# Sandshark_3D_-_MCU_-_ATSAM3X8C.net
KiCad netlist of a schematic drawn in Altium Designer
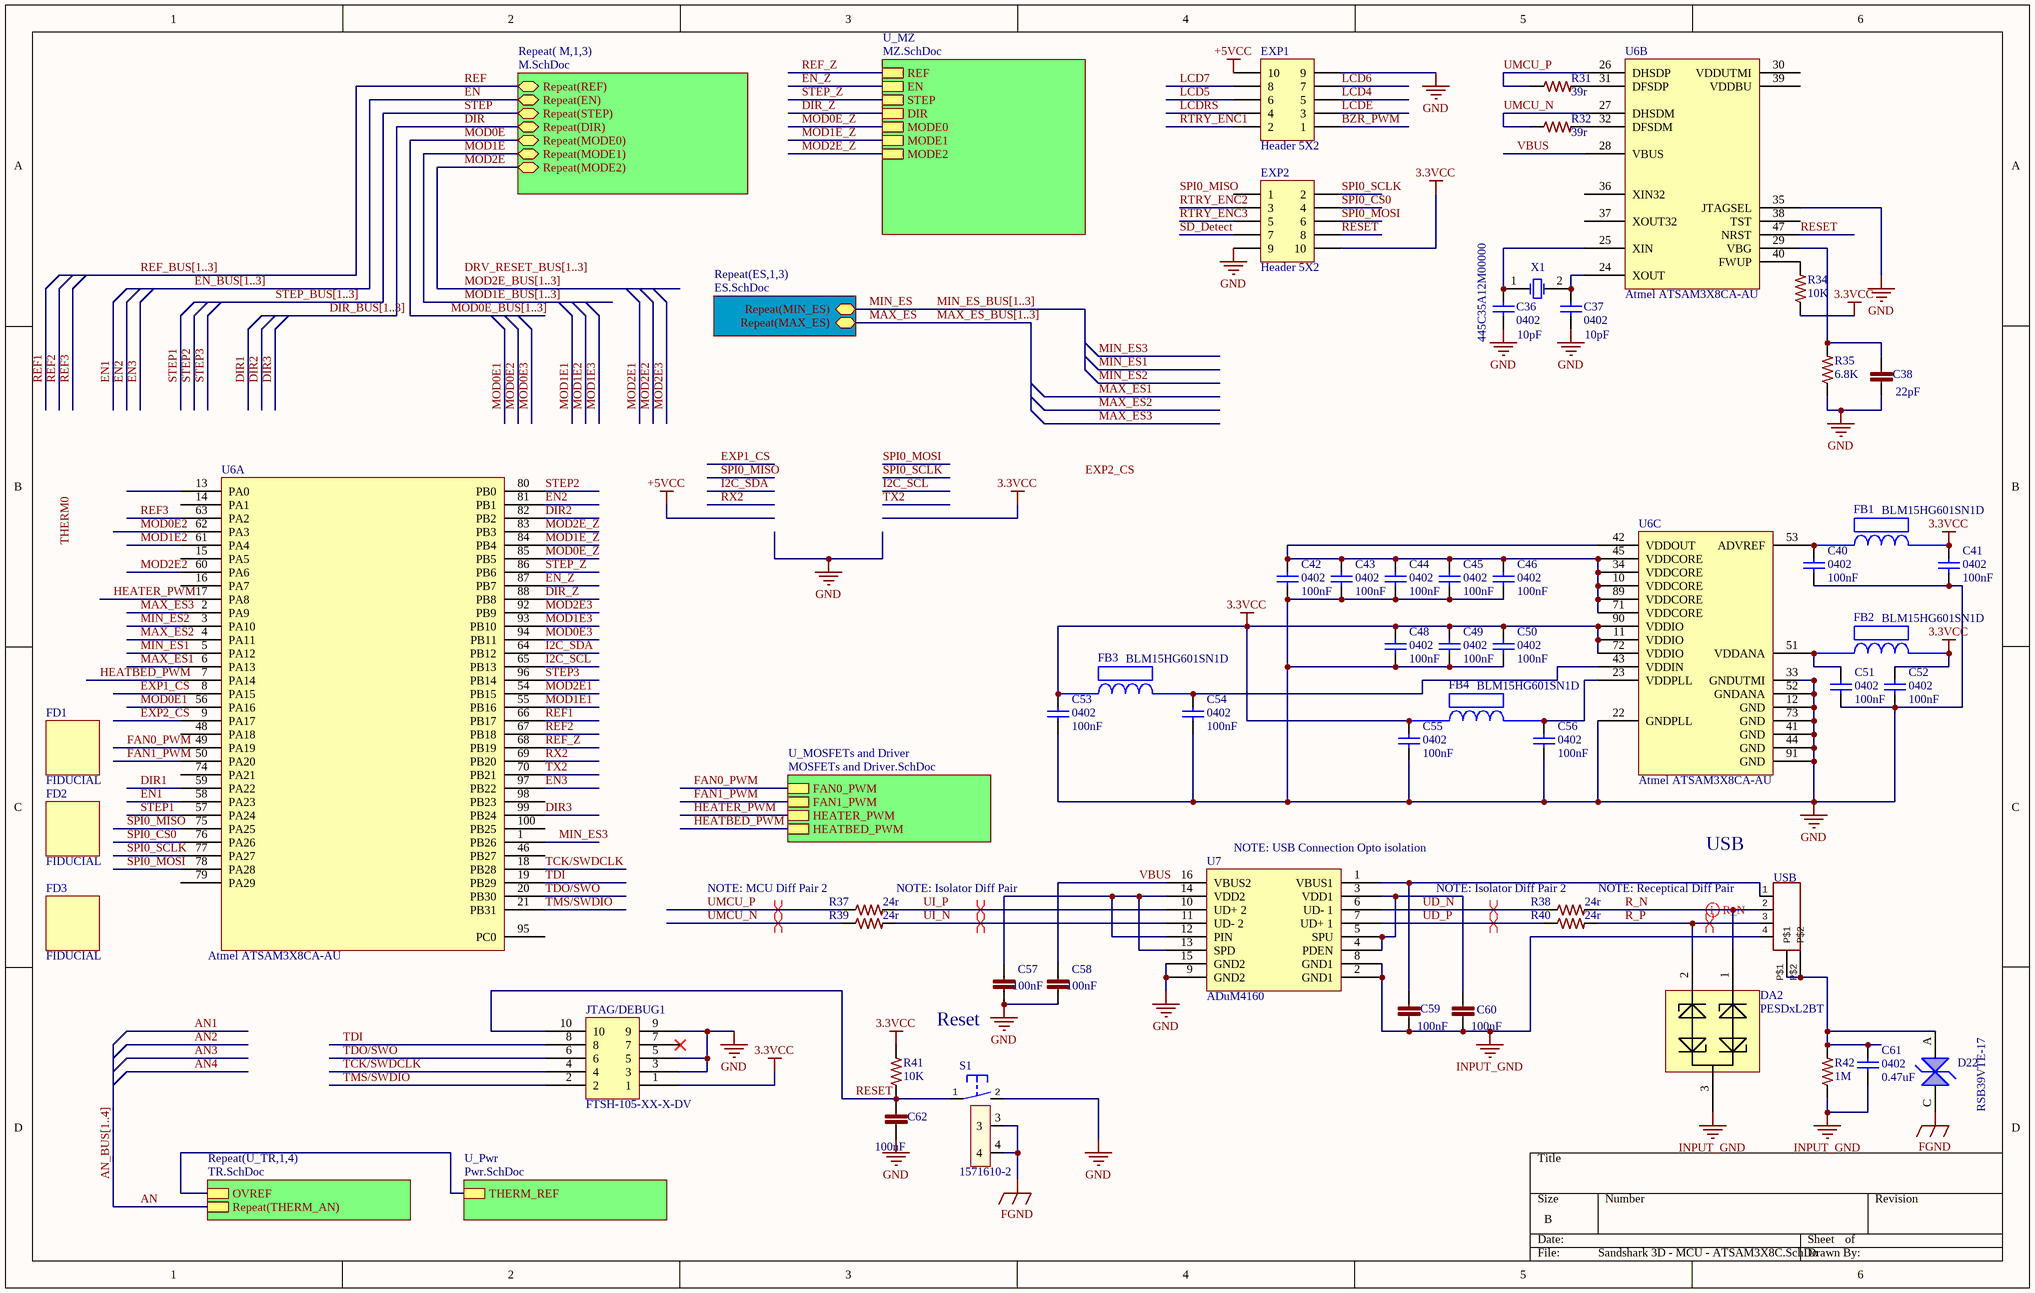
[diagram p0: Sandshark 3D - MCU - ATSAM3X8C.SchDoc]

(export (version "E")
  (design (tool "Eeschema 10.0.6"))
  (components
    (comp (ref "C36")
      (value "0402")
      (footprint "C0402")
      (description "CAP CER 10PF 50V 5% NP0 0402")
      (fields
        (field (name "MFR PART #") "CL05C100JB5NNNC")
        (field (name "MFR") "Samsung")
        (field (name "ALTIUM_VALUE") "10pF")
        (field (name "PUBLISHER") "Ultimachine")
      )
      (libsource (lib "Tigershark3D") (part "CL05C100JB5NNNC"))
    )
    (comp (ref "C37")
      (value "0402")
      (footprint "C0402")
      (description "CAP CER 10PF 50V 5% NP0 0402")
      (fields
        (field (name "MFR PART #") "CL05C100JB5NNNC")
        (field (name "MFR") "Samsung")
        (field (name "ALTIUM_VALUE") "10pF")
        (field (name "PUBLISHER") "Ultimachine")
      )
      (libsource (lib "Tigershark3D") (part "CL05C100JB5NNNC"))
    )
    (comp (ref "C38")
      (value "22pF")
      (footprint "C0402")
      (description "CAP CER 0402 22pF 50V 5% C0G")
      (fields
        (field (name "MANUFACTURERPARTNUMBER") "04025A220JAT2A")
        (field (name "PUBLISHER") "UltiMachine")
      )
      (libsource (lib "3Delight") (part "04025A220JAT2A"))
    )
    (comp (ref "C40")
      (value "100nF")
      (footprint "C0402")
      (description "CAP CER 0.1UF (100nF) 16V 10% X7R 0402")
      (fields
        (field (name "MFR PART #") "GRM155R71C104KA88D")
        (field (name "MFR") "Murata")
        (field (name "PACKAGEREFERENCE") "0402")
        (field (name "PUBLISHER") "Ultimachine")
      )
      (libsource (lib "Tigershark3D") (part "GRM155R71C104KA88D"))
    )
    (comp (ref "C41")
      (value "100nF")
      (footprint "C0402")
      (description "CAP CER 0.1UF (100nF) 16V 10% X7R 0402")
      (fields
        (field (name "MFR PART #") "GRM155R71C104KA88D")
        (field (name "MFR") "Murata")
        (field (name "PACKAGEREFERENCE") "0402")
        (field (name "PUBLISHER") "Ultimachine")
      )
      (libsource (lib "Tigershark3D") (part "GRM155R71C104KA88D"))
    )
    (comp (ref "C42")
      (value "100nF")
      (footprint "C0402")
      (description "CAP CER 0.1UF (100nF) 16V 10% X7R 0402")
      (fields
        (field (name "MFR PART #") "GRM155R71C104KA88D")
        (field (name "MFR") "Murata")
        (field (name "PACKAGEREFERENCE") "0402")
        (field (name "PUBLISHER") "Ultimachine")
      )
      (libsource (lib "Tigershark3D") (part "GRM155R71C104KA88D"))
    )
    (comp (ref "C43")
      (value "100nF")
      (footprint "C0402")
      (description "CAP CER 0.1UF (100nF) 16V 10% X7R 0402")
      (fields
        (field (name "MFR PART #") "GRM155R71C104KA88D")
        (field (name "MFR") "Murata")
        (field (name "PACKAGEREFERENCE") "0402")
        (field (name "PUBLISHER") "Ultimachine")
      )
      (libsource (lib "Tigershark3D") (part "GRM155R71C104KA88D"))
    )
    (comp (ref "C44")
      (value "100nF")
      (footprint "C0402")
      (description "CAP CER 0.1UF (100nF) 16V 10% X7R 0402")
      (fields
        (field (name "MFR PART #") "GRM155R71C104KA88D")
        (field (name "MFR") "Murata")
        (field (name "PACKAGEREFERENCE") "0402")
        (field (name "PUBLISHER") "Ultimachine")
      )
      (libsource (lib "Tigershark3D") (part "GRM155R71C104KA88D"))
    )
    (comp (ref "C45")
      (value "100nF")
      (footprint "C0402")
      (description "CAP CER 0.1UF (100nF) 16V 10% X7R 0402")
      (fields
        (field (name "MFR PART #") "GRM155R71C104KA88D")
        (field (name "MFR") "Murata")
        (field (name "PACKAGEREFERENCE") "0402")
        (field (name "PUBLISHER") "Ultimachine")
      )
      (libsource (lib "Tigershark3D") (part "GRM155R71C104KA88D"))
    )
    (comp (ref "C46")
      (value "100nF")
      (footprint "C0402")
      (description "CAP CER 0.1UF (100nF) 16V 10% X7R 0402")
      (fields
        (field (name "MFR PART #") "GRM155R71C104KA88D")
        (field (name "MFR") "Murata")
        (field (name "PACKAGEREFERENCE") "0402")
        (field (name "PUBLISHER") "Ultimachine")
      )
      (libsource (lib "Tigershark3D") (part "GRM155R71C104KA88D"))
    )
    (comp (ref "C48")
      (value "100nF")
      (footprint "C0402")
      (description "CAP CER 0.1UF (100nF) 16V 10% X7R 0402")
      (fields
        (field (name "MFR PART #") "GRM155R71C104KA88D")
        (field (name "MFR") "Murata")
        (field (name "PACKAGEREFERENCE") "0402")
        (field (name "PUBLISHER") "Ultimachine")
      )
      (libsource (lib "Tigershark3D") (part "GRM155R71C104KA88D"))
    )
    (comp (ref "C49")
      (value "100nF")
      (footprint "C0402")
      (description "CAP CER 0.1UF (100nF) 16V 10% X7R 0402")
      (fields
        (field (name "MFR PART #") "GRM155R71C104KA88D")
        (field (name "MFR") "Murata")
        (field (name "PACKAGEREFERENCE") "0402")
        (field (name "PUBLISHER") "Ultimachine")
      )
      (libsource (lib "Tigershark3D") (part "GRM155R71C104KA88D"))
    )
    (comp (ref "C50")
      (value "100nF")
      (footprint "C0402")
      (description "CAP CER 0.1UF (100nF) 16V 10% X7R 0402")
      (fields
        (field (name "MFR PART #") "GRM155R71C104KA88D")
        (field (name "MFR") "Murata")
        (field (name "PACKAGEREFERENCE") "0402")
        (field (name "PUBLISHER") "Ultimachine")
      )
      (libsource (lib "Tigershark3D") (part "GRM155R71C104KA88D"))
    )
    (comp (ref "C51")
      (value "100nF")
      (footprint "C0402")
      (description "CAP CER 0.1UF (100nF) 16V 10% X7R 0402")
      (fields
        (field (name "MFR PART #") "GRM155R71C104KA88D")
        (field (name "MFR") "Murata")
        (field (name "PACKAGEREFERENCE") "0402")
        (field (name "PUBLISHER") "Ultimachine")
      )
      (libsource (lib "Tigershark3D") (part "GRM155R71C104KA88D"))
    )
    (comp (ref "C52")
      (value "100nF")
      (footprint "C0402")
      (description "CAP CER 0.1UF (100nF) 16V 10% X7R 0402")
      (fields
        (field (name "MFR PART #") "GRM155R71C104KA88D")
        (field (name "MFR") "Murata")
        (field (name "PACKAGEREFERENCE") "0402")
        (field (name "PUBLISHER") "Ultimachine")
      )
      (libsource (lib "Tigershark3D") (part "GRM155R71C104KA88D"))
    )
    (comp (ref "C53")
      (value "100nF")
      (footprint "C0402")
      (description "CAP CER 0.1UF (100nF) 16V 10% X7R 0402")
      (fields
        (field (name "MFR PART #") "GRM155R71C104KA88D")
        (field (name "MFR") "Murata")
        (field (name "PACKAGEREFERENCE") "0402")
        (field (name "PUBLISHER") "Ultimachine")
      )
      (libsource (lib "Tigershark3D") (part "GRM155R71C104KA88D"))
    )
    (comp (ref "C54")
      (value "100nF")
      (footprint "C0402")
      (description "CAP CER 0.1UF (100nF) 16V 10% X7R 0402")
      (fields
        (field (name "MFR PART #") "GRM155R71C104KA88D")
        (field (name "MFR") "Murata")
        (field (name "PACKAGEREFERENCE") "0402")
        (field (name "PUBLISHER") "Ultimachine")
      )
      (libsource (lib "Tigershark3D") (part "GRM155R71C104KA88D"))
    )
    (comp (ref "C55")
      (value "100nF")
      (footprint "C0402")
      (description "CAP CER 0.1UF (100nF) 16V 10% X7R 0402")
      (fields
        (field (name "MFR PART #") "GRM155R71C104KA88D")
        (field (name "MFR") "Murata")
        (field (name "PACKAGEREFERENCE") "0402")
        (field (name "PUBLISHER") "Ultimachine")
      )
      (libsource (lib "Tigershark3D") (part "GRM155R71C104KA88D"))
    )
    (comp (ref "C56")
      (value "100nF")
      (footprint "C0402")
      (description "CAP CER 0.1UF (100nF) 16V 10% X7R 0402")
      (fields
        (field (name "MFR PART #") "GRM155R71C104KA88D")
        (field (name "MFR") "Murata")
        (field (name "PACKAGEREFERENCE") "0402")
        (field (name "PUBLISHER") "Ultimachine")
      )
      (libsource (lib "Tigershark3D") (part "GRM155R71C104KA88D"))
    )
    (comp (ref "C57")
      (value "100nF")
      (footprint "C0402")
      (description "CAP CER 0402 100nF 16V 10% X7R")
      (fields
        (field (name "MANUFACTURERPARTNUMBER") "GRM155R71C104KA88D")
        (field (name "PUBLISHER") "UltiMachine")
      )
      (libsource (lib "3Delight") (part "GRM155R71C104KA88D"))
    )
    (comp (ref "C58")
      (value "100nF")
      (footprint "C0402")
      (description "CAP CER 0402 100nF 16V 10% X7R")
      (fields
        (field (name "MANUFACTURERPARTNUMBER") "GRM155R71C104KA88D")
        (field (name "PUBLISHER") "UltiMachine")
      )
      (libsource (lib "3Delight") (part "GRM155R71C104KA88D"))
    )
    (comp (ref "C59")
      (value "100nF")
      (footprint "C0402")
      (description "CAP CER 0402 100nF 16V 10% X7R")
      (fields
        (field (name "MANUFACTURERPARTNUMBER") "GRM155R71C104KA88D")
        (field (name "PUBLISHER") "UltiMachine")
      )
      (libsource (lib "3Delight") (part "GRM155R71C104KA88D"))
    )
    (comp (ref "C60")
      (value "100nF")
      (footprint "C0402")
      (description "CAP CER 0402 100nF 16V 10% X7R")
      (fields
        (field (name "MANUFACTURERPARTNUMBER") "GRM155R71C104KA88D")
        (field (name "PUBLISHER") "UltiMachine")
      )
      (libsource (lib "3Delight") (part "GRM155R71C104KA88D"))
    )
    (comp (ref "C61")
      (value "0.47uF")
      (footprint "C0402")
      (description "0.47uF 6.3v C0402 - GRM155R60J474KE19D")
      (fields
        (field (name "MFR PART #") "GRM155R60J474KE19D")
        (field (name "MFR") "Murata")
        (field (name "PACKAGEREFERENCE") "0402")
        (field (name "PUBLISHER") "Ultimachine")
      )
      (libsource (lib "Tigershark3D") (part "GRM155R60J474KE19D"))
    )
    (comp (ref "C62")
      (value "100nF")
      (footprint "C0402")
      (description "CAP CER 0402 100nF 16V 10% X7R")
      (fields
        (field (name "MANUFACTURERPARTNUMBER") "GRM155R71C104KA88D")
        (field (name "PUBLISHER") "UltiMachine")
      )
      (libsource (lib "3Delight") (part "GRM155R71C104KA88D"))
    )
    (comp (ref "D22")
      (value "RSB39VTE-17")
      (footprint "SOD323-R")
      (description "DIODE TVS")
      (libsource (lib "Tigershark3D") (part "RSB39VTE-17"))
    )
    (comp (ref "DA2")
      (value "PESDxL2BT")
      (footprint "SOT95P230X110-3N")
      (description "PESDxL2BT TVS Diode Array 2x")
      (libsource (lib "Tigershark3D") (part "PESDxL2BT"))
    )
    (comp (ref "EXP1")
      (value "Header 5X2")
      (footprint "HDR2X5")
      (description "Header, 5-Pin, Dual row")
      (fields (field (name "PUBLISHER") "Altium Limited"))
      (libsource (lib "") (part "Header 5X2_1"))
    )
    (comp (ref "EXP2")
      (value "Header 5X2")
      (footprint "HDR2X5")
      (description "Header, 5-Pin, Dual row")
      (fields (field (name "PUBLISHER") "Altium Limited"))
      (libsource (lib "Miscellaneous Connectors") (part "Header 5X2"))
    )
    (comp (ref "FB1")
      (value "BLM15HG601SN1D")
      (footprint "BLM18PG121SN1D")
      (libsource (lib "AHD Part Library") (part "BLM15HG601SN1D"))
    )
    (comp (ref "FB2")
      (value "BLM15HG601SN1D")
      (footprint "BLM18PG121SN1D")
      (libsource (lib "AHD Part Library") (part "BLM15HG601SN1D"))
    )
    (comp (ref "FB3")
      (value "BLM15HG601SN1D")
      (footprint "BLM18PG121SN1D")
      (libsource (lib "AHD Part Library") (part "BLM15HG601SN1D"))
    )
    (comp (ref "FB4")
      (value "BLM15HG601SN1D")
      (footprint "BLM18PG121SN1D")
      (libsource (lib "AHD Part Library") (part "BLM15HG601SN1D"))
    )
    (comp (ref "FD1")
      (value "FIDUCIAL")
      (footprint "FIDUCIAL-1X2")
      (libsource (lib "ZMBo Schematic Library") (part "FIDUCIAL"))
    )
    (comp (ref "FD2")
      (value "FIDUCIAL")
      (footprint "FIDUCIAL-1X2")
      (libsource (lib "ZMBo Schematic Library") (part "FIDUCIAL"))
    )
    (comp (ref "FD3")
      (value "FIDUCIAL")
      (footprint "FIDUCIAL-1X2")
      (libsource (lib "ZMBo Schematic Library") (part "FIDUCIAL"))
    )
    (comp (ref "JTAG/DEBUG1")
      (value "FTSH-105-XX-X-DV")
      (footprint "FTSH-105-XX-X-DV")
      (libsource (lib "Adams Altium Library") (part "ARM Cortex JTAG-DEBUG Header"))
    )
    (comp (ref "R31")
      (value "39r")
      (footprint "R0402")
      (description "RES SMD 39 OHM 1% 1/10W 0402")
      (fields
        (field (name "MANUFACTURER") "Panasonic")
        (field (name "MANUFACTURERPARTNUMBER") "ERJ-2RKF39R0X")
        (field (name "PUBLISHER") "UltiMachine")
      )
      (libsource (lib "Tigershark3D") (part "ERJ-2RKF39R0X"))
    )
    (comp (ref "R32")
      (value "39r")
      (footprint "R0402")
      (description "RES SMD 39 OHM 1% 1/10W 0402")
      (fields
        (field (name "MANUFACTURER") "Panasonic")
        (field (name "MANUFACTURERPARTNUMBER") "ERJ-2RKF39R0X")
        (field (name "PUBLISHER") "UltiMachine")
      )
      (libsource (lib "Tigershark3D") (part "ERJ-2RKF39R0X"))
    )
    (comp (ref "R34")
      (value "10K")
      (footprint "R0603")
      (description "RES 0603 10K 100mW 1%")
      (fields
        (field (name "MANUFACTURERPARTNUMBER") "ERJ-3EKF1002V")
        (field (name "PUBLISHER") "UltiMachine")
      )
      (libsource (lib "Tigershark3D") (part "ERJ-3EKF1002V"))
    )
    (comp (ref "R35")
      (value "6.8K")
      (footprint "R0402")
      (description "RES SMD 6.8K OHM 1% 1/16W 0402")
      (fields
        (field (name "MANUFACTURER") "Vishay Dale")
        (field (name "MANUFACTURERPARTNUMBER") "CRCW04026K80FKED")
        (field (name "PUBLISHER") "UltiMachine")
      )
      (libsource (lib "Tigershark3D") (part "CRCW04026K80FKED"))
    )
    (comp (ref "R37")
      (value "24r")
      (footprint "R0603")
      (description "RES SMD 24 OHM 1% 1/10W 0603")
      (fields
        (field (name "MANUFACTURER") "Samsung")
        (field (name "MANUFACTURERPARTNUMBER") "RC0603FR-07100KL")
        (field (name "PUBLISHER") "UltiMachine")
      )
      (libsource (lib "Tigershark3D") (part "RC1608F240CS"))
    )
    (comp (ref "R38")
      (value "24r")
      (footprint "R0603")
      (description "RES SMD 24 OHM 1% 1/10W 0603")
      (fields
        (field (name "MANUFACTURER") "Samsung")
        (field (name "MANUFACTURERPARTNUMBER") "RC0603FR-07100KL")
        (field (name "PUBLISHER") "UltiMachine")
      )
      (libsource (lib "Tigershark3D") (part "RC1608F240CS"))
    )
    (comp (ref "R39")
      (value "24r")
      (footprint "R0603")
      (description "RES SMD 24 OHM 1% 1/10W 0603")
      (fields
        (field (name "MANUFACTURER") "Samsung")
        (field (name "MANUFACTURERPARTNUMBER") "RC0603FR-07100KL")
        (field (name "PUBLISHER") "UltiMachine")
      )
      (libsource (lib "Tigershark3D") (part "RC1608F240CS"))
    )
    (comp (ref "R40")
      (value "24r")
      (footprint "R0603")
      (description "RES SMD 24 OHM 1% 1/10W 0603")
      (fields
        (field (name "MANUFACTURER") "Samsung")
        (field (name "MANUFACTURERPARTNUMBER") "RC0603FR-07100KL")
        (field (name "PUBLISHER") "UltiMachine")
      )
      (libsource (lib "Tigershark3D") (part "RC1608F240CS"))
    )
    (comp (ref "R41")
      (value "10K")
      (footprint "R0603")
      (description "RES 0603 10K 100mW 1%")
      (fields
        (field (name "MANUFACTURERPARTNUMBER") "ERJ-3EKF1002V")
        (field (name "PUBLISHER") "UltiMachine")
      )
      (libsource (lib "3Delight") (part "ERJ-3EKF1002V"))
    )
    (comp (ref "R42")
      (value "1M")
      (footprint "R0402")
      (description "RES 0402 1M 100mW 5%")
      (fields (field (name "MANUFACTURERPARTNUMBER") "ERJ2GEJ105X") (field (name "PUBLISHER") "UltiMachine"))
      (libsource (lib "Tigershark3D") (part "ERJ2GEJ105X"))
    )
    (comp (ref "S1")
      (value "1571610-2")
      (footprint "B3F-31XX")
      (description "SWTCH Momentary Washable")
      (fields
        (field (name "MANUFACTURER") "Omron")
        (field (name "MANUFACTURER_1") "TE")
        (field (name "PUBLISHER") "UltiMachine")
      )
      (libsource (lib "ZMBo Schematic Library") (part "1571610-2_1"))
    )
    (comp (ref "U6")
      (value "Atmel ATSAM3X8CA-AU")
      (footprint "ATSAM3X8CA-AU TQFP100")
      (description "Atmel ARM Cortex M3 MCU ATSAM3X8CA-AU")
      (fields (field (name "MANUFACTURE PART #") "ATSAM3X8CA-AU"))
      (libsource (lib "Tigershark3D") (part "ATML-ATSAM3X8CA-AU-LQFP-100"))
    )
    (comp (ref "U7")
      (value "ADuM4160")
      (footprint "ADUM4160BRWZ-RL")
      (description "ADI iCoupler - USB 2.0 Galvanic Isolator")
      (libsource (lib "Tigershark3D") (part "ADuM4160"))
    )
    (comp (ref "USB")
      (value "USB-B")
      (footprint "PN61729")
      (description "USB connector B PTH")
      (fields (field (name "PUBLISHER") "UltiMachine"))
      (libsource (lib "3Delight") (part "USB-B"))
    )
    (comp (ref "X1")
      (value "445C35A12M00000")
      (footprint "445C35A12M00000")
      (description "Crystal Oscillator")
      (fields (field (name "PUBLISHER") "Altium Limited"))
      (libsource (lib "Miscellaneous Devices") (part "XTAL"))
    )
  )
  (nets
    (net (code "35") (name "+5VCC") (class "Default")
      (node (ref "EXP1") (pin "10") (pinfunction "10_10") (pintype "passive"))
    )
    (net (code "42") (name "/BZR_PWM") (class "Default")
      (node (ref "EXP1") (pin "1") (pinfunction "1_1") (pintype "passive"))
    )
    (net (code "44") (name "/DIR1") (class "Default")
      (node (ref "U6") (pin "59") (pinfunction "PA22_59") (pintype "passive"))
    )
    (net (code "45") (name "/DIR2") (class "Default")
      (node (ref "U6") (pin "82") (pinfunction "PB2_82") (pintype "passive"))
    )
    (net (code "46") (name "/DIR3") (class "Default")
      (node (ref "U6") (pin "99") (pinfunction "PB24_99") (pintype "passive"))
    )
    (net (code "48") (name "/DIR_Z") (class "Default")
      (node (ref "U6") (pin "88") (pinfunction "PB8_88") (pintype "passive"))
    )
    (net (code "51") (name "/EN1") (class "Default")
      (node (ref "U6") (pin "58") (pinfunction "PA23_58") (pintype "passive"))
    )
    (net (code "52") (name "/EN2") (class "Default")
      (node (ref "U6") (pin "81") (pinfunction "PB1_81") (pintype "passive"))
    )
    (net (code "53") (name "/EN3") (class "Default")
      (node (ref "U6") (pin "97") (pinfunction "PB22_97") (pintype "passive"))
    )
    (net (code "55") (name "/EN_Z") (class "Default")
      (node (ref "U6") (pin "87") (pinfunction "PB7_87") (pintype "passive"))
    )
    (net (code "56") (name "/EXP1_CS") (class "Default")
      (node (ref "U6") (pin "8") (pinfunction "PA15_8") (pintype "passive"))
    )
    (net (code "57") (name "/EXP2_CS") (class "Default")
      (node (ref "U6") (pin "9") (pinfunction "PA17_9") (pintype "passive"))
    )
    (net (code "58") (name "/FAN0_PWM") (class "Default")
      (node (ref "U6") (pin "49") (pinfunction "PA19_49") (pintype "passive"))
    )
    (net (code "59") (name "/FAN1_PWM") (class "Default")
      (node (ref "U6") (pin "50") (pinfunction "PA20_50") (pintype "passive"))
    )
    (net (code "60") (name "/HEATBED_PWM") (class "Default")
      (node (ref "U6") (pin "7") (pinfunction "PA14_7") (pintype "passive"))
    )
    (net (code "61") (name "/HEATER_PWM") (class "Default")
      (node (ref "U6") (pin "17") (pinfunction "PA8_17") (pintype "passive"))
    )
    (net (code "62") (name "/I2C_SCL") (class "Default")
      (node (ref "U6") (pin "65") (pinfunction "PB13_65") (pintype "passive"))
    )
    (net (code "63") (name "/I2C_SDA") (class "Default")
      (node (ref "U6") (pin "64") (pinfunction "PB12_64") (pintype "passive"))
    )
    (net (code "64") (name "/LCD4") (class "Default")
      (node (ref "EXP1") (pin "5") (pinfunction "5_5") (pintype "passive"))
    )
    (net (code "65") (name "/LCD5") (class "Default")
      (node (ref "EXP1") (pin "6") (pinfunction "6_6") (pintype "passive"))
    )
    (net (code "66") (name "/LCD6") (class "Default")
      (node (ref "EXP1") (pin "7") (pinfunction "7_7") (pintype "passive"))
    )
    (net (code "67") (name "/LCD7") (class "Default")
      (node (ref "EXP1") (pin "8") (pinfunction "8_8") (pintype "passive"))
    )
    (net (code "68") (name "/LCDE") (class "Default")
      (node (ref "EXP1") (pin "3") (pinfunction "3_3") (pintype "passive"))
    )
    (net (code "69") (name "/LCDRS") (class "Default")
      (node (ref "EXP1") (pin "4") (pinfunction "4_4") (pintype "passive"))
    )
    (net (code "71") (name "/MAX_ES1") (class "Default")
      (node (ref "U6") (pin "6") (pinfunction "PA13_6") (pintype "passive"))
    )
    (net (code "72") (name "/MAX_ES2") (class "Default")
      (node (ref "U6") (pin "4") (pinfunction "PA11_4") (pintype "passive"))
    )
    (net (code "73") (name "/MAX_ES3") (class "Default")
      (node (ref "U6") (pin "2") (pinfunction "PA9_2") (pintype "passive"))
    )
    (net (code "76") (name "/MIN_ES1") (class "Default")
      (node (ref "U6") (pin "5") (pinfunction "PA12_5") (pintype "passive"))
    )
    (net (code "77") (name "/MIN_ES2") (class "Default")
      (node (ref "U6") (pin "3") (pinfunction "PA10_3") (pintype "passive"))
    )
    (net (code "78") (name "/MIN_ES3") (class "Default")
      (node (ref "U6") (pin "1") (pinfunction "PB26_1") (pintype "passive"))
    )
    (net (code "81") (name "/MOD0E1") (class "Default")
      (node (ref "U6") (pin "56") (pinfunction "PA16_56") (pintype "passive"))
    )
    (net (code "82") (name "/MOD0E2") (class "Default")
      (node (ref "U6") (pin "62") (pinfunction "PA3_62") (pintype "passive"))
    )
    (net (code "83") (name "/MOD0E3") (class "Default")
      (node (ref "U6") (pin "94") (pinfunction "PB11_94") (pintype "passive"))
    )
    (net (code "85") (name "/MOD0E_Z") (class "Default")
      (node (ref "U6") (pin "85") (pinfunction "PB5_85") (pintype "passive"))
    )
    (net (code "87") (name "/MOD1E1") (class "Default")
      (node (ref "U6") (pin "55") (pinfunction "PB16_55") (pintype "passive"))
    )
    (net (code "88") (name "/MOD1E2") (class "Default")
      (node (ref "U6") (pin "61") (pinfunction "PA4_61") (pintype "passive"))
    )
    (net (code "89") (name "/MOD1E3") (class "Default")
      (node (ref "U6") (pin "93") (pinfunction "PB10_93") (pintype "passive"))
    )
    (net (code "91") (name "/MOD1E_Z") (class "Default")
      (node (ref "U6") (pin "84") (pinfunction "PB4_84") (pintype "passive"))
    )
    (net (code "93") (name "/MOD2E1") (class "Default")
      (node (ref "U6") (pin "54") (pinfunction "PB15_54") (pintype "passive"))
    )
    (net (code "94") (name "/MOD2E2") (class "Default")
      (node (ref "U6") (pin "60") (pinfunction "PA6_60") (pintype "passive"))
    )
    (net (code "95") (name "/MOD2E3") (class "Default")
      (node (ref "U6") (pin "92") (pinfunction "PB9_92") (pintype "passive"))
    )
    (net (code "97") (name "/MOD2E_Z") (class "Default")
      (node (ref "U6") (pin "83") (pinfunction "PB3_83") (pintype "passive"))
    )
    (net (code "100") (name "/REF1") (class "Default")
      (node (ref "U6") (pin "66") (pinfunction "PB17_66") (pintype "passive"))
    )
    (net (code "101") (name "/REF2") (class "Default")
      (node (ref "U6") (pin "67") (pinfunction "PB18_67") (pintype "passive"))
    )
    (net (code "102") (name "/REF3") (class "Default")
      (node (ref "U6") (pin "63") (pinfunction "PA2_63") (pintype "passive"))
    )
    (net (code "104") (name "/REF_Z") (class "Default")
      (node (ref "U6") (pin "68") (pinfunction "PB19_68") (pintype "passive"))
    )
    (net (code "105") (name "/RESET") (class "Default")
      (node (ref "C62") (pin "1") (pinfunction "1_1") (pintype "passive"))
      (node (ref "EXP2") (pin "8") (pinfunction "8_8") (pintype "passive"))
      (node (ref "JTAG/DEBUG1") (pin "10") (pinfunction "10_10") (pintype "passive"))
      (node (ref "R41") (pin "1") (pinfunction "1_1") (pintype "passive"))
      (node (ref "S1") (pin "1") (pinfunction "P_1") (pintype "passive"))
      (node (ref "U6") (pin "47") (pinfunction "NRST_47") (pintype "passive"))
    )
    (net (code "106") (name "/RTRY_ENC1") (class "Default")
      (node (ref "EXP1") (pin "2") (pinfunction "2_2") (pintype "passive"))
    )
    (net (code "107") (name "/RTRY_ENC2") (class "Default")
      (node (ref "EXP2") (pin "3") (pinfunction "3_3") (pintype "passive"))
    )
    (net (code "108") (name "/RTRY_ENC3") (class "Default")
      (node (ref "EXP2") (pin "5") (pinfunction "5_5") (pintype "passive"))
    )
    (net (code "109") (name "/RX2") (class "Default")
      (node (ref "U6") (pin "69") (pinfunction "PB20_69") (pintype "passive"))
    )
    (net (code "110") (name "/R_N") (class "Default")
      (node (ref "DA2") (pin "1") (pinfunction "1_1") (pintype "passive"))
      (node (ref "R38") (pin "2") (pinfunction "2_2") (pintype "passive"))
      (node (ref "USB") (pin "2") (pinfunction "2_2") (pintype "passive"))
    )
    (net (code "111") (name "/R_P") (class "Default")
      (node (ref "DA2") (pin "2") (pinfunction "2_2") (pintype "passive"))
      (node (ref "R40") (pin "2") (pinfunction "2_2") (pintype "passive"))
      (node (ref "USB") (pin "3") (pinfunction "3_3") (pintype "passive"))
    )
    (net (code "112") (name "/SD_Detect") (class "Default")
      (node (ref "EXP2") (pin "7") (pinfunction "7_7") (pintype "passive"))
    )
    (net (code "113") (name "/SPI0_CS0") (class "Default")
      (node (ref "EXP2") (pin "4") (pinfunction "4_4") (pintype "passive"))
      (node (ref "U6") (pin "76") (pinfunction "PA26_76") (pintype "passive"))
    )
    (net (code "114") (name "/SPI0_MISO") (class "Default")
      (node (ref "U6") (pin "75") (pinfunction "PA25_75") (pintype "passive"))
    )
    (net (code "115") (name "/SPI0_MOSI") (class "Default")
      (node (ref "EXP2") (pin "6") (pinfunction "6_6") (pintype "passive"))
      (node (ref "U6") (pin "78") (pinfunction "PA28_78") (pintype "passive"))
    )
    (net (code "116") (name "/SPI0_SCLK") (class "Default")
      (node (ref "EXP2") (pin "2") (pinfunction "2_2") (pintype "passive"))
      (node (ref "U6") (pin "77") (pinfunction "PA27_77") (pintype "passive"))
    )
    (net (code "118") (name "/STEP1") (class "Default")
      (node (ref "U6") (pin "57") (pinfunction "PA24_57") (pintype "passive"))
    )
    (net (code "119") (name "/STEP2") (class "Default")
      (node (ref "U6") (pin "80") (pinfunction "PB0_80") (pintype "passive"))
    )
    (net (code "120") (name "/STEP3") (class "Default")
      (node (ref "U6") (pin "96") (pinfunction "PB14_96") (pintype "passive"))
    )
    (net (code "122") (name "/STEP_Z") (class "Default")
      (node (ref "U6") (pin "86") (pinfunction "PB6_86") (pintype "passive"))
    )
    (net (code "123") (name "/TCK{slash}SWDCLK") (class "Default")
      (node (ref "JTAG/DEBUG1") (pin "4") (pinfunction "4_4") (pintype "passive"))
      (node (ref "U6") (pin "18") (pinfunction "PB28_18") (pintype "passive"))
    )
    (net (code "124") (name "/TDI") (class "Default")
      (node (ref "JTAG/DEBUG1") (pin "8") (pinfunction "8_8") (pintype "passive"))
      (node (ref "U6") (pin "19") (pinfunction "PB29_19") (pintype "passive"))
    )
    (net (code "125") (name "/TDO{slash}SWO") (class "Default")
      (node (ref "JTAG/DEBUG1") (pin "6") (pinfunction "6_6") (pintype "passive"))
      (node (ref "U6") (pin "20") (pinfunction "PB30_20") (pintype "passive"))
    )
    (net (code "127") (name "/TMS{slash}SWDIO") (class "Default")
      (node (ref "JTAG/DEBUG1") (pin "2") (pinfunction "2_2") (pintype "passive"))
      (node (ref "U6") (pin "21") (pinfunction "PB31_21") (pintype "passive"))
    )
    (net (code "128") (name "/TX2") (class "Default")
      (node (ref "U6") (pin "70") (pinfunction "PB21_70") (pintype "passive"))
    )
    (net (code "129") (name "/UD_N") (class "Default")
      (node (ref "R38") (pin "1") (pinfunction "1_1") (pintype "passive"))
      (node (ref "U7") (pin "6") (pinfunction "UD-_1_6") (pintype "passive"))
    )
    (net (code "130") (name "/UD_P") (class "Default")
      (node (ref "R40") (pin "1") (pinfunction "1_1") (pintype "passive"))
      (node (ref "U7") (pin "7") (pinfunction "UD+_1_7") (pintype "passive"))
    )
    (net (code "131") (name "/UI_N") (class "Default")
      (node (ref "R39") (pin "2") (pinfunction "2_2") (pintype "passive"))
      (node (ref "U7") (pin "11") (pinfunction "UD-_2_11") (pintype "passive"))
    )
    (net (code "132") (name "/UI_P") (class "Default")
      (node (ref "R37") (pin "2") (pinfunction "2_2") (pintype "passive"))
      (node (ref "U7") (pin "10") (pinfunction "UD+_2_10") (pintype "passive"))
    )
    (net (code "133") (name "/UMCU_N") (class "Default")
      (node (ref "R32") (pin "1") (pinfunction "1_1") (pintype "passive"))
      (node (ref "R39") (pin "1") (pinfunction "1_1") (pintype "passive"))
      (node (ref "U6") (pin "27") (pinfunction "DHSDM_27") (pintype "passive"))
    )
    (net (code "134") (name "/UMCU_P") (class "Default")
      (node (ref "R31") (pin "1") (pinfunction "1_1") (pintype "passive"))
      (node (ref "R37") (pin "1") (pinfunction "1_1") (pintype "passive"))
      (node (ref "U6") (pin "26") (pinfunction "DHSDP_26") (pintype "passive"))
    )
    (net (code "135") (name "/VBUS") (class "Default")
      (node (ref "C58") (pin "1") (pinfunction "1_1") (pintype "passive"))
      (node (ref "U6") (pin "28") (pinfunction "VBUS_28") (pintype "passive"))
      (node (ref "U7") (pin "16") (pinfunction "VBUS2_16") (pintype "passive"))
    )
    (net (code "136") (name "3.3VCC") (class "Default")
      (node (ref "C41") (pin "2") (pinfunction "2_2") (pintype "passive"))
      (node (ref "C48") (pin "2") (pinfunction "2_2") (pintype "passive"))
      (node (ref "C49") (pin "2") (pinfunction "2_2") (pintype "passive"))
      (node (ref "C50") (pin "2") (pinfunction "2_2") (pintype "passive"))
      (node (ref "C52") (pin "2") (pinfunction "2_2") (pintype "passive"))
      (node (ref "C53") (pin "2") (pinfunction "2_2") (pintype "passive"))
      (node (ref "C55") (pin "2") (pinfunction "2_2") (pintype "passive"))
      (node (ref "EXP2") (pin "10") (pinfunction "10_10") (pintype "passive"))
      (node (ref "FB1") (pin "2") (pinfunction "2_2") (pintype "passive"))
      (node (ref "FB2") (pin "2") (pinfunction "2_2") (pintype "passive"))
      (node (ref "FB3") (pin "1") (pinfunction "1_1") (pintype "passive"))
      (node (ref "FB4") (pin "1") (pinfunction "1_1") (pintype "passive"))
      (node (ref "JTAG/DEBUG1") (pin "1") (pinfunction "1_1") (pintype "passive"))
      (node (ref "R34") (pin "1") (pinfunction "1_1") (pintype "passive"))
      (node (ref "R41") (pin "2") (pinfunction "2_2") (pintype "passive"))
      (node (ref "U6") (pin "11") (pinfunction "VDDIO_11") (pintype "passive"))
      (node (ref "U6") (pin "72") (pinfunction "VDDIO_72") (pintype "passive"))
      (node (ref "U6") (pin "90") (pinfunction "VDDIO_90") (pintype "passive"))
    )
    (net (code "137") (name "FGND") (class "Default")
      (node (ref "D22") (pin "C") (pinfunction "C_C") (pintype "power_in"))
      (node (ref "S1") (pin "3") (pinfunction "3_3") (pintype "power_in"))
      (node (ref "S1") (pin "4") (pinfunction "4_4") (pintype "power_in"))
    )
    (net (code "138") (name "GND") (class "Default")
      (node (ref "C36") (pin "1") (pinfunction "1_1") (pintype "passive"))
      (node (ref "C37") (pin "1") (pinfunction "1_1") (pintype "passive"))
      (node (ref "C38") (pin "2") (pinfunction "2_2") (pintype "passive"))
      (node (ref "C40") (pin "1") (pinfunction "1_1") (pintype "passive"))
      (node (ref "C41") (pin "1") (pinfunction "1_1") (pintype "passive"))
      (node (ref "C42") (pin "1") (pinfunction "1_1") (pintype "passive"))
      (node (ref "C43") (pin "1") (pinfunction "1_1") (pintype "passive"))
      (node (ref "C44") (pin "1") (pinfunction "1_1") (pintype "passive"))
      (node (ref "C45") (pin "1") (pinfunction "1_1") (pintype "passive"))
      (node (ref "C46") (pin "1") (pinfunction "1_1") (pintype "passive"))
      (node (ref "C48") (pin "1") (pinfunction "1_1") (pintype "passive"))
      (node (ref "C49") (pin "1") (pinfunction "1_1") (pintype "passive"))
      (node (ref "C50") (pin "1") (pinfunction "1_1") (pintype "passive"))
      (node (ref "C51") (pin "1") (pinfunction "1_1") (pintype "passive"))
      (node (ref "C52") (pin "1") (pinfunction "1_1") (pintype "passive"))
      (node (ref "C53") (pin "1") (pinfunction "1_1") (pintype "passive"))
      (node (ref "C54") (pin "1") (pinfunction "1_1") (pintype "passive"))
      (node (ref "C55") (pin "1") (pinfunction "1_1") (pintype "passive"))
      (node (ref "C56") (pin "1") (pinfunction "1_1") (pintype "passive"))
      (node (ref "C57") (pin "2") (pinfunction "2_2") (pintype "passive"))
      (node (ref "C58") (pin "2") (pinfunction "2_2") (pintype "passive"))
      (node (ref "C62") (pin "2") (pinfunction "2_2") (pintype "passive"))
      (node (ref "EXP1") (pin "9") (pinfunction "9_9") (pintype "passive"))
      (node (ref "EXP2") (pin "9") (pinfunction "9_9") (pintype "passive"))
      (node (ref "JTAG/DEBUG1") (pin "3") (pinfunction "3_3") (pintype "passive"))
      (node (ref "JTAG/DEBUG1") (pin "5") (pinfunction "5_5") (pintype "passive"))
      (node (ref "JTAG/DEBUG1") (pin "9") (pinfunction "9_9") (pintype "passive"))
      (node (ref "R35") (pin "1") (pinfunction "1_1") (pintype "passive"))
      (node (ref "S1") (pin "2") (pinfunction "S_2") (pintype "passive"))
      (node (ref "U6") (pin "12") (pinfunction "GND_12") (pintype "passive"))
      (node (ref "U6") (pin "22") (pinfunction "GNDPLL_22") (pintype "passive"))
      (node (ref "U6") (pin "33") (pinfunction "GNDUTMI_33") (pintype "passive"))
      (node (ref "U6") (pin "35") (pinfunction "JTAGSEL_35") (pintype "passive"))
      (node (ref "U6") (pin "41") (pinfunction "GND_41") (pintype "passive"))
      (node (ref "U6") (pin "44") (pinfunction "GND_44") (pintype "passive"))
      (node (ref "U6") (pin "52") (pinfunction "GNDANA_52") (pintype "passive"))
      (node (ref "U6") (pin "73") (pinfunction "GND_73") (pintype "passive"))
      (node (ref "U6") (pin "91") (pinfunction "GND_91") (pintype "passive"))
      (node (ref "U7") (pin "15") (pinfunction "GND2_15") (pintype "passive"))
      (node (ref "U7") (pin "9") (pinfunction "GND2_9") (pintype "passive"))
    )
    (net (code "139") (name "INPUT_GND") (class "Default")
      (node (ref "C59") (pin "2") (pinfunction "2_2") (pintype "passive"))
      (node (ref "C60") (pin "2") (pinfunction "2_2") (pintype "passive"))
      (node (ref "C61") (pin "1") (pinfunction "1_1") (pintype "passive"))
      (node (ref "DA2") (pin "3") (pinfunction "3_3") (pintype "passive"))
      (node (ref "R42") (pin "1") (pinfunction "1_1") (pintype "passive"))
      (node (ref "U7") (pin "2") (pinfunction "GND1_2") (pintype "passive"))
      (node (ref "U7") (pin "8") (pinfunction "GND1_8") (pintype "passive"))
      (node (ref "USB") (pin "4") (pinfunction "4_4") (pintype "passive"))
    )
    (net (code "140") (name "Net-(C61-Pad2)") (class "Default")
      (node (ref "C61") (pin "2") (pinfunction "2_2") (pintype "passive"))
      (node (ref "D22") (pin "A") (pinfunction "A_A") (pintype "power_in"))
      (node (ref "R42") (pin "2") (pinfunction "2_2") (pintype "passive"))
      (node (ref "USB") (pin "P$1") (pinfunction "P$1_P$1") (pintype "passive"))
      (node (ref "USB") (pin "P$2") (pinfunction "P$2_P$2") (pintype "passive"))
    )
    (net (code "141") (name "Net-(U6B-DFSDM)") (class "Default")
      (node (ref "R32") (pin "2") (pinfunction "2_2") (pintype "passive"))
      (node (ref "U6") (pin "32") (pinfunction "DFSDM_32") (pintype "passive"))
    )
    (net (code "142") (name "Net-(U6B-DFSDP)") (class "Default")
      (node (ref "R31") (pin "2") (pinfunction "2_2") (pintype "passive"))
      (node (ref "U6") (pin "31") (pinfunction "DFSDP_31") (pintype "passive"))
    )
    (net (code "143") (name "Net-(U6B-FWUP)") (class "Default")
      (node (ref "R34") (pin "2") (pinfunction "2_2") (pintype "passive"))
      (node (ref "U6") (pin "40") (pinfunction "FWUP_40") (pintype "passive"))
    )
    (net (code "144") (name "Net-(U6B-VBG)") (class "Default")
      (node (ref "C38") (pin "1") (pinfunction "1_1") (pintype "passive"))
      (node (ref "R35") (pin "2") (pinfunction "2_2") (pintype "passive"))
      (node (ref "U6") (pin "29") (pinfunction "VBG_29") (pintype "passive"))
    )
    (net (code "145") (name "Net-(U6B-XIN)") (class "Default")
      (node (ref "C36") (pin "2") (pinfunction "2_2") (pintype "passive"))
      (node (ref "U6") (pin "25") (pinfunction "XIN_25") (pintype "passive"))
      (node (ref "X1") (pin "1") (pinfunction "OSC1_1") (pintype "passive"))
    )
    (net (code "146") (name "Net-(U6B-XOUT)") (class "Default")
      (node (ref "C37") (pin "2") (pinfunction "2_2") (pintype "passive"))
      (node (ref "U6") (pin "24") (pinfunction "XOUT_24") (pintype "passive"))
      (node (ref "X1") (pin "2") (pinfunction "OSC2_2") (pintype "passive"))
    )
    (net (code "147") (name "Net-(U6C-ADVREF)") (class "Default")
      (node (ref "C40") (pin "2") (pinfunction "2_2") (pintype "passive"))
      (node (ref "FB1") (pin "1") (pinfunction "1_1") (pintype "passive"))
      (node (ref "U6") (pin "53") (pinfunction "ADVREF_53") (pintype "passive"))
    )
    (net (code "148") (name "Net-(U6C-VDDANA)") (class "Default")
      (node (ref "C51") (pin "2") (pinfunction "2_2") (pintype "passive"))
      (node (ref "FB2") (pin "1") (pinfunction "1_1") (pintype "passive"))
      (node (ref "U6") (pin "51") (pinfunction "VDDANA_51") (pintype "passive"))
    )
    (net (code "149") (name "Net-(U6C-VDDIN)") (class "Default")
      (node (ref "C54") (pin "2") (pinfunction "2_2") (pintype "passive"))
      (node (ref "FB3") (pin "2") (pinfunction "2_2") (pintype "passive"))
      (node (ref "U6") (pin "43") (pinfunction "VDDIN_43") (pintype "passive"))
    )
    (net (code "150") (name "Net-(U6C-VDDOUT)") (class "Default")
      (node (ref "C42") (pin "2") (pinfunction "2_2") (pintype "passive"))
      (node (ref "C43") (pin "2") (pinfunction "2_2") (pintype "passive"))
      (node (ref "C44") (pin "2") (pinfunction "2_2") (pintype "passive"))
      (node (ref "C45") (pin "2") (pinfunction "2_2") (pintype "passive"))
      (node (ref "C46") (pin "2") (pinfunction "2_2") (pintype "passive"))
      (node (ref "U6") (pin "10") (pinfunction "VDDCORE_10") (pintype "passive"))
      (node (ref "U6") (pin "34") (pinfunction "VDDCORE_34") (pintype "passive"))
      (node (ref "U6") (pin "42") (pinfunction "VDDOUT_42") (pintype "passive"))
      (node (ref "U6") (pin "45") (pinfunction "VDDCORE_45") (pintype "passive"))
      (node (ref "U6") (pin "71") (pinfunction "VDDCORE_71") (pintype "passive"))
      (node (ref "U6") (pin "89") (pinfunction "VDDCORE_89") (pintype "passive"))
    )
    (net (code "151") (name "Net-(U6C-VDDPLL)") (class "Default")
      (node (ref "C56") (pin "2") (pinfunction "2_2") (pintype "passive"))
      (node (ref "FB4") (pin "2") (pinfunction "2_2") (pintype "passive"))
      (node (ref "U6") (pin "23") (pinfunction "VDDPLL_23") (pintype "passive"))
    )
    (net (code "152") (name "Net-(U7-PDEN)") (class "Default")
      (node (ref "C60") (pin "1") (pinfunction "1_1") (pintype "passive"))
      (node (ref "U7") (pin "3") (pinfunction "VDD1_3") (pintype "passive"))
      (node (ref "U7") (pin "4") (pinfunction "PDEN_4") (pintype "passive"))
      (node (ref "U7") (pin "5") (pinfunction "SPU_5") (pintype "passive"))
    )
    (net (code "153") (name "Net-(U7-PIN)") (class "Default")
      (node (ref "C57") (pin "1") (pinfunction "1_1") (pintype "passive"))
      (node (ref "U7") (pin "12") (pinfunction "PIN_12") (pintype "passive"))
      (node (ref "U7") (pin "13") (pinfunction "SPD_13") (pintype "passive"))
      (node (ref "U7") (pin "14") (pinfunction "VDD2_14") (pintype "passive"))
    )
    (net (code "154") (name "Net-(U7-VBUS1)") (class "Default")
      (node (ref "C59") (pin "1") (pinfunction "1_1") (pintype "passive"))
      (node (ref "U7") (pin "1") (pinfunction "VBUS1_1") (pintype "passive"))
      (node (ref "USB") (pin "1") (pinfunction "1_1") (pintype "passive"))
    )
    (net (code "155") (name "unconnected-(EXP2-Pad1)") (class "Default")
      (node (ref "EXP2") (pin "1") (pinfunction "1_1") (pintype "passive"))
    )
    (net (code "156") (name "unconnected-(JTAG/DEBUG1-Pad7)") (class "Default")
      (node (ref "JTAG/DEBUG1") (pin "7") (pinfunction "7_7") (pintype "passive+no_connect"))
    )
    (net (code "157") (name "unconnected-(U6A-PA0-Pad13)") (class "Default")
      (node (ref "U6") (pin "13") (pinfunction "PA0_13") (pintype "passive"))
    )
    (net (code "158") (name "unconnected-(U6A-PA1-Pad14)") (class "Default")
      (node (ref "U6") (pin "14") (pinfunction "PA1_14") (pintype "passive"))
    )
    (net (code "159") (name "unconnected-(U6A-PA5-Pad15)") (class "Default")
      (node (ref "U6") (pin "15") (pinfunction "PA5_15") (pintype "passive"))
    )
    (net (code "160") (name "unconnected-(U6A-PA7-Pad16)") (class "Default")
      (node (ref "U6") (pin "16") (pinfunction "PA7_16") (pintype "passive"))
    )
    (net (code "161") (name "unconnected-(U6A-PA18-Pad48)") (class "Default")
      (node (ref "U6") (pin "48") (pinfunction "PA18_48") (pintype "passive"))
    )
    (net (code "162") (name "unconnected-(U6A-PA21-Pad74)") (class "Default")
      (node (ref "U6") (pin "74") (pinfunction "PA21_74") (pintype "passive"))
    )
    (net (code "163") (name "unconnected-(U6A-PA29-Pad79)") (class "Default")
      (node (ref "U6") (pin "79") (pinfunction "PA29_79") (pintype "passive"))
    )
    (net (code "164") (name "unconnected-(U6A-PB23-Pad98)") (class "Default")
      (node (ref "U6") (pin "98") (pinfunction "PB23_98") (pintype "passive"))
    )
    (net (code "165") (name "unconnected-(U6A-PB25-Pad100)") (class "Default")
      (node (ref "U6") (pin "100") (pinfunction "PB25_100") (pintype "passive"))
    )
    (net (code "166") (name "unconnected-(U6A-PB27-Pad46)") (class "Default")
      (node (ref "U6") (pin "46") (pinfunction "PB27_46") (pintype "passive"))
    )
    (net (code "167") (name "unconnected-(U6A-PC0-Pad95)") (class "Default")
      (node (ref "U6") (pin "95") (pinfunction "PC0_95") (pintype "passive"))
    )
    (net (code "168") (name "unconnected-(U6B-TST-Pad38)") (class "Default")
      (node (ref "U6") (pin "38") (pinfunction "TST_38") (pintype "passive"))
    )
    (net (code "169") (name "unconnected-(U6B-VDDBU-Pad39)") (class "Default")
      (node (ref "U6") (pin "39") (pinfunction "VDDBU_39") (pintype "passive"))
    )
    (net (code "170") (name "unconnected-(U6B-VDDUTMI-Pad30)") (class "Default")
      (node (ref "U6") (pin "30") (pinfunction "VDDUTMI_30") (pintype "passive"))
    )
    (net (code "171") (name "unconnected-(U6B-XIN32-Pad36)") (class "Default")
      (node (ref "U6") (pin "36") (pinfunction "XIN32_36") (pintype "passive"))
    )
    (net (code "172") (name "unconnected-(U6B-XOUT32-Pad37)") (class "Default")
      (node (ref "U6") (pin "37") (pinfunction "XOUT32_37") (pintype "passive"))
    )
  )
)
